# Lights.net
KiCad netlist of a schematic drawn in Altium Designer
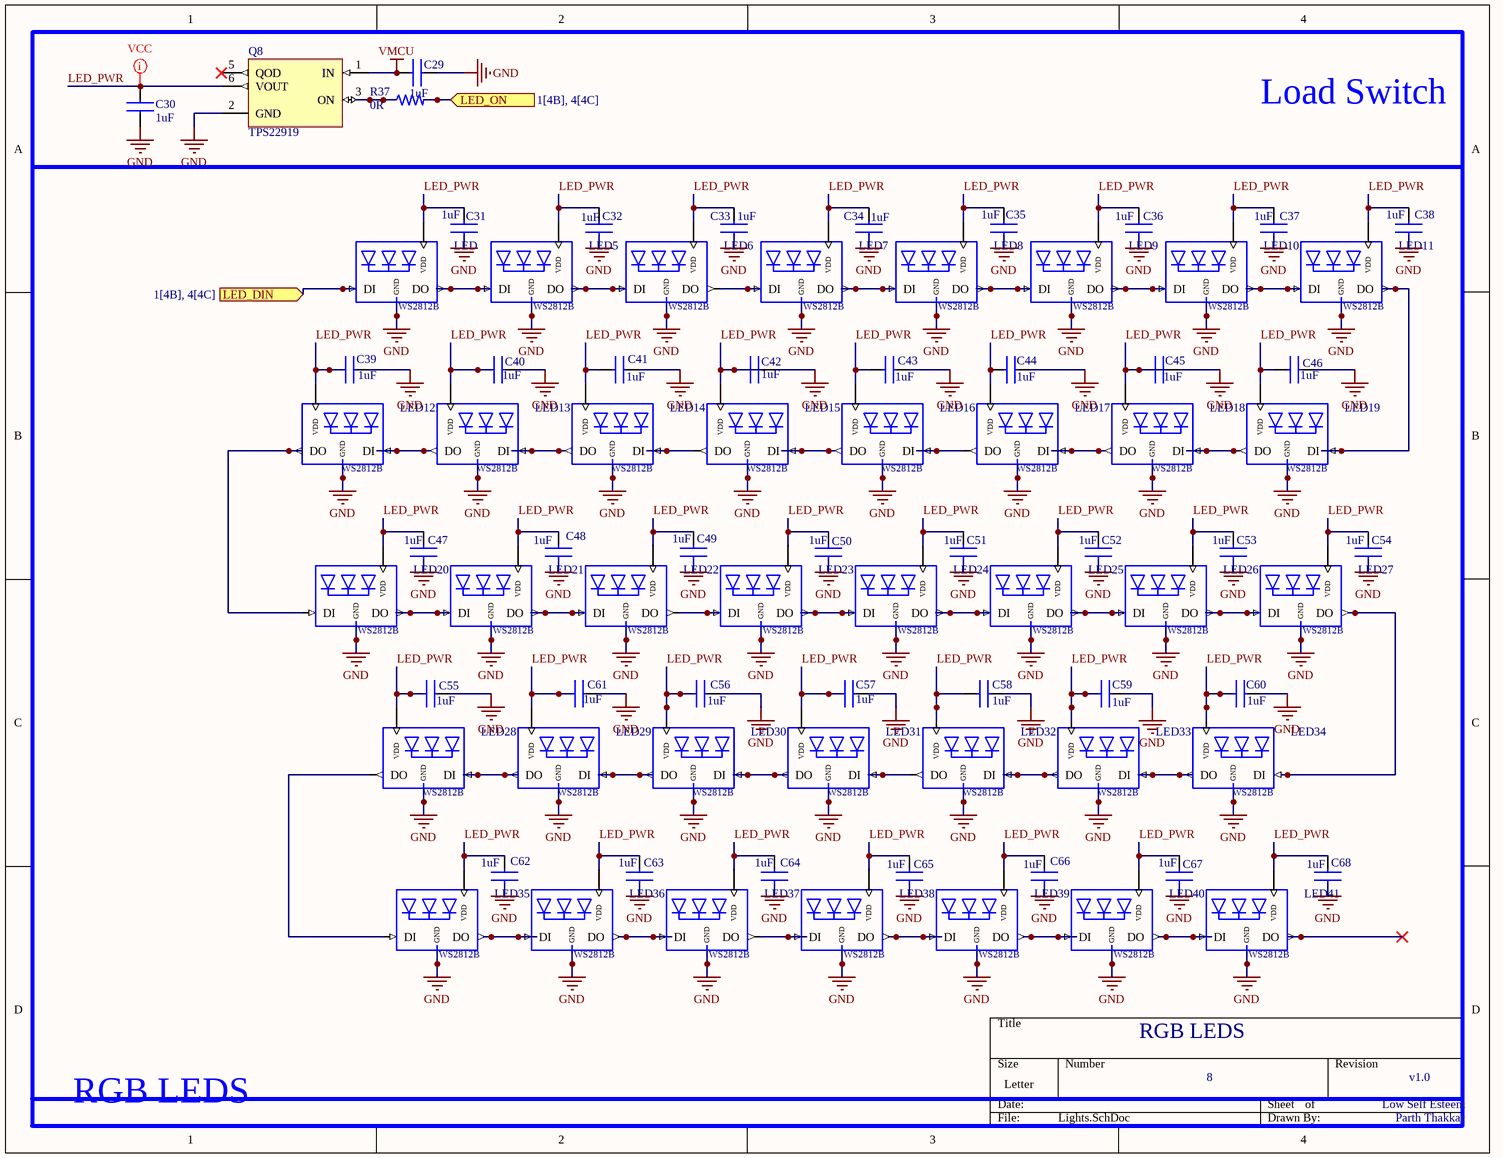
[diagram p0: Lights.SchDoc]

(export (version "E")
  (design (tool "Eeschema 10.0.6"))
  (components
    (comp (ref "C29")
      (value "1uF")
      (footprint "Capacitor 0603")
      (fields
        (field (name "MANUFACTURER") "Murata")
        (field (name "MANUFACTURER PART NUMBER") "GRM188R61A105KA61D")
        (field (name "Comment") "CAP 1uF 10V 0603")
      )
      (libsource (lib "Keyboard_parts") (part "CAP 1uF 10V 0603"))
    )
    (comp (ref "C30")
      (value "1uF")
      (footprint "CAPACITOR 0805")
      (description "Multilayer Ceramic Capacitor, 1 uF, 10 V, ± 20%, X5R, 0201 [0603 Metric]")
      (fields
        (field (name "MANUFACTURER") "Murata")
        (field (name "MANUFACTURER PART NUMBER") "GRM033R61A105ME15D")
      )
      (libsource (lib "Keyboard_parts") (part "CAP 47uF 10V 0805"))
    )
    (comp (ref "C31")
      (value "1uF")
      (footprint "Capacitor 0603")
      (fields
        (field (name "MANUFACTURER") "Murata")
        (field (name "MANUFACTURER PART NUMBER") "GRM188R61A105KA61D")
        (field (name "Comment") "CAP 1uF 10V 0603")
      )
      (libsource (lib "Keyboard_parts") (part "CAP 1uF 10V 0603"))
    )
    (comp (ref "C32")
      (value "1uF")
      (footprint "Capacitor 0603")
      (fields
        (field (name "MANUFACTURER") "Murata")
        (field (name "MANUFACTURER PART NUMBER") "GRM188R61A105KA61D")
        (field (name "Comment") "CAP 1uF 10V 0603")
      )
      (libsource (lib "Keyboard_parts") (part "CAP 1uF 10V 0603"))
    )
    (comp (ref "C33")
      (value "1uF")
      (footprint "Capacitor 0603")
      (fields
        (field (name "MANUFACTURER") "Murata")
        (field (name "MANUFACTURER PART NUMBER") "GRM188R61A105KA61D")
        (field (name "Comment") "CAP 1uF 10V 0603")
      )
      (libsource (lib "Keyboard_parts") (part "CAP 1uF 10V 0603"))
    )
    (comp (ref "C34")
      (value "1uF")
      (footprint "Capacitor 0603")
      (fields
        (field (name "MANUFACTURER") "Murata")
        (field (name "MANUFACTURER PART NUMBER") "GRM188R61A105KA61D")
        (field (name "Comment") "CAP 1uF 10V 0603")
      )
      (libsource (lib "Keyboard_parts") (part "CAP 1uF 10V 0603"))
    )
    (comp (ref "C35")
      (value "1uF")
      (footprint "Capacitor 0603")
      (fields
        (field (name "MANUFACTURER") "Murata")
        (field (name "MANUFACTURER PART NUMBER") "GRM188R61A105KA61D")
        (field (name "Comment") "CAP 1uF 10V 0603")
      )
      (libsource (lib "Keyboard_parts") (part "CAP 1uF 10V 0603"))
    )
    (comp (ref "C36")
      (value "1uF")
      (footprint "Capacitor 0603")
      (fields
        (field (name "MANUFACTURER") "Murata")
        (field (name "MANUFACTURER PART NUMBER") "GRM188R61A105KA61D")
        (field (name "Comment") "CAP 1uF 10V 0603")
      )
      (libsource (lib "Keyboard_parts") (part "CAP 1uF 10V 0603"))
    )
    (comp (ref "C37")
      (value "1uF")
      (footprint "Capacitor 0603")
      (fields
        (field (name "MANUFACTURER") "Murata")
        (field (name "MANUFACTURER PART NUMBER") "GRM188R61A105KA61D")
        (field (name "Comment") "CAP 1uF 10V 0603")
      )
      (libsource (lib "Keyboard_parts") (part "CAP 1uF 10V 0603"))
    )
    (comp (ref "C38")
      (value "1uF")
      (footprint "Capacitor 0603")
      (fields
        (field (name "MANUFACTURER") "Murata")
        (field (name "MANUFACTURER PART NUMBER") "GRM188R61A105KA61D")
        (field (name "Comment") "CAP 1uF 10V 0603")
      )
      (libsource (lib "Keyboard_parts") (part "CAP 1uF 10V 0603"))
    )
    (comp (ref "C39")
      (value "1uF")
      (footprint "Capacitor 0603")
      (fields
        (field (name "MANUFACTURER") "Murata")
        (field (name "MANUFACTURER PART NUMBER") "GRM188R61A105KA61D")
        (field (name "Comment") "CAP 1uF 10V 0603")
      )
      (libsource (lib "Keyboard_parts") (part "CAP 1uF 10V 0603"))
    )
    (comp (ref "C40")
      (value "1uF")
      (footprint "Capacitor 0603")
      (fields
        (field (name "MANUFACTURER") "Murata")
        (field (name "MANUFACTURER PART NUMBER") "GRM188R61A105KA61D")
        (field (name "Comment") "CAP 1uF 10V 0603")
      )
      (libsource (lib "Keyboard_parts") (part "CAP 1uF 10V 0603"))
    )
    (comp (ref "C41")
      (value "1uF")
      (footprint "Capacitor 0603")
      (fields
        (field (name "MANUFACTURER") "Murata")
        (field (name "MANUFACTURER PART NUMBER") "GRM188R61A105KA61D")
        (field (name "Comment") "CAP 1uF 10V 0603")
      )
      (libsource (lib "Keyboard_parts") (part "CAP 1uF 10V 0603"))
    )
    (comp (ref "C42")
      (value "1uF")
      (footprint "Capacitor 0603")
      (fields
        (field (name "MANUFACTURER") "Murata")
        (field (name "MANUFACTURER PART NUMBER") "GRM188R61A105KA61D")
        (field (name "Comment") "CAP 1uF 10V 0603")
      )
      (libsource (lib "Keyboard_parts") (part "CAP 1uF 10V 0603"))
    )
    (comp (ref "C43")
      (value "1uF")
      (footprint "Capacitor 0603")
      (fields
        (field (name "MANUFACTURER") "Murata")
        (field (name "MANUFACTURER PART NUMBER") "GRM188R61A105KA61D")
        (field (name "Comment") "CAP 1uF 10V 0603")
      )
      (libsource (lib "Keyboard_parts") (part "CAP 1uF 10V 0603"))
    )
    (comp (ref "C44")
      (value "1uF")
      (footprint "Capacitor 0603")
      (fields
        (field (name "MANUFACTURER") "Murata")
        (field (name "MANUFACTURER PART NUMBER") "GRM188R61A105KA61D")
        (field (name "Comment") "CAP 1uF 10V 0603")
      )
      (libsource (lib "Keyboard_parts") (part "CAP 1uF 10V 0603"))
    )
    (comp (ref "C45")
      (value "1uF")
      (footprint "Capacitor 0603")
      (fields
        (field (name "MANUFACTURER") "Murata")
        (field (name "MANUFACTURER PART NUMBER") "GRM188R61A105KA61D")
        (field (name "Comment") "CAP 1uF 10V 0603")
      )
      (libsource (lib "Keyboard_parts") (part "CAP 1uF 10V 0603"))
    )
    (comp (ref "C46")
      (value "1uF")
      (footprint "Capacitor 0603")
      (fields
        (field (name "MANUFACTURER") "Murata")
        (field (name "MANUFACTURER PART NUMBER") "GRM188R61A105KA61D")
        (field (name "Comment") "CAP 1uF 10V 0603")
      )
      (libsource (lib "Keyboard_parts") (part "CAP 1uF 10V 0603"))
    )
    (comp (ref "C47")
      (value "1uF")
      (footprint "Capacitor 0603")
      (fields
        (field (name "MANUFACTURER") "Murata")
        (field (name "MANUFACTURER PART NUMBER") "GRM188R61A105KA61D")
        (field (name "Comment") "CAP 1uF 10V 0603")
      )
      (libsource (lib "Keyboard_parts") (part "CAP 1uF 10V 0603"))
    )
    (comp (ref "C48")
      (value "1uF")
      (footprint "Capacitor 0603")
      (fields
        (field (name "MANUFACTURER") "Murata")
        (field (name "MANUFACTURER PART NUMBER") "GRM188R61A105KA61D")
        (field (name "Comment") "CAP 1uF 10V 0603")
      )
      (libsource (lib "Keyboard_parts") (part "CAP 1uF 10V 0603"))
    )
    (comp (ref "C49")
      (value "1uF")
      (footprint "Capacitor 0603")
      (fields
        (field (name "MANUFACTURER") "Murata")
        (field (name "MANUFACTURER PART NUMBER") "GRM188R61A105KA61D")
        (field (name "Comment") "CAP 1uF 10V 0603")
      )
      (libsource (lib "Keyboard_parts") (part "CAP 1uF 10V 0603"))
    )
    (comp (ref "C50")
      (value "1uF")
      (footprint "Capacitor 0603")
      (fields
        (field (name "MANUFACTURER") "Murata")
        (field (name "MANUFACTURER PART NUMBER") "GRM188R61A105KA61D")
        (field (name "Comment") "CAP 1uF 10V 0603")
      )
      (libsource (lib "Keyboard_parts") (part "CAP 1uF 10V 0603"))
    )
    (comp (ref "C51")
      (value "1uF")
      (footprint "Capacitor 0603")
      (fields
        (field (name "MANUFACTURER") "Murata")
        (field (name "MANUFACTURER PART NUMBER") "GRM188R61A105KA61D")
        (field (name "Comment") "CAP 1uF 10V 0603")
      )
      (libsource (lib "Keyboard_parts") (part "CAP 1uF 10V 0603"))
    )
    (comp (ref "C52")
      (value "1uF")
      (footprint "Capacitor 0603")
      (fields
        (field (name "MANUFACTURER") "Murata")
        (field (name "MANUFACTURER PART NUMBER") "GRM188R61A105KA61D")
        (field (name "Comment") "CAP 1uF 10V 0603")
      )
      (libsource (lib "Keyboard_parts") (part "CAP 1uF 10V 0603"))
    )
    (comp (ref "C53")
      (value "1uF")
      (footprint "Capacitor 0603")
      (fields
        (field (name "MANUFACTURER") "Murata")
        (field (name "MANUFACTURER PART NUMBER") "GRM188R61A105KA61D")
        (field (name "Comment") "CAP 1uF 10V 0603")
      )
      (libsource (lib "Keyboard_parts") (part "CAP 1uF 10V 0603"))
    )
    (comp (ref "C54")
      (value "1uF")
      (footprint "Capacitor 0603")
      (fields
        (field (name "MANUFACTURER") "Murata")
        (field (name "MANUFACTURER PART NUMBER") "GRM188R61A105KA61D")
        (field (name "Comment") "CAP 1uF 10V 0603")
      )
      (libsource (lib "Keyboard_parts") (part "CAP 1uF 10V 0603"))
    )
    (comp (ref "C55")
      (value "1uF")
      (footprint "Capacitor 0603")
      (fields
        (field (name "MANUFACTURER") "Murata")
        (field (name "MANUFACTURER PART NUMBER") "GRM188R61A105KA61D")
        (field (name "Comment") "CAP 1uF 10V 0603")
      )
      (libsource (lib "Keyboard_parts") (part "CAP 1uF 10V 0603"))
    )
    (comp (ref "C56")
      (value "1uF")
      (footprint "Capacitor 0603")
      (fields
        (field (name "MANUFACTURER") "Murata")
        (field (name "MANUFACTURER PART NUMBER") "GRM188R61A105KA61D")
        (field (name "Comment") "CAP 1uF 10V 0603")
      )
      (libsource (lib "Keyboard_parts") (part "CAP 1uF 10V 0603"))
    )
    (comp (ref "C57")
      (value "1uF")
      (footprint "Capacitor 0603")
      (fields
        (field (name "MANUFACTURER") "Murata")
        (field (name "MANUFACTURER PART NUMBER") "GRM188R61A105KA61D")
        (field (name "Comment") "CAP 1uF 10V 0603")
      )
      (libsource (lib "Keyboard_parts") (part "CAP 1uF 10V 0603"))
    )
    (comp (ref "C58")
      (value "1uF")
      (footprint "Capacitor 0603")
      (fields
        (field (name "MANUFACTURER") "Murata")
        (field (name "MANUFACTURER PART NUMBER") "GRM188R61A105KA61D")
        (field (name "Comment") "CAP 1uF 10V 0603")
      )
      (libsource (lib "Keyboard_parts") (part "CAP 1uF 10V 0603"))
    )
    (comp (ref "C59")
      (value "1uF")
      (footprint "Capacitor 0603")
      (fields
        (field (name "MANUFACTURER") "Murata")
        (field (name "MANUFACTURER PART NUMBER") "GRM188R61A105KA61D")
        (field (name "Comment") "CAP 1uF 10V 0603")
      )
      (libsource (lib "Keyboard_parts") (part "CAP 1uF 10V 0603"))
    )
    (comp (ref "C60")
      (value "1uF")
      (footprint "Capacitor 0603")
      (fields
        (field (name "MANUFACTURER") "Murata")
        (field (name "MANUFACTURER PART NUMBER") "GRM188R61A105KA61D")
        (field (name "Comment") "CAP 1uF 10V 0603")
      )
      (libsource (lib "Keyboard_parts") (part "CAP 1uF 10V 0603"))
    )
    (comp (ref "C61")
      (value "1uF")
      (footprint "Capacitor 0603")
      (fields
        (field (name "MANUFACTURER") "Murata")
        (field (name "MANUFACTURER PART NUMBER") "GRM188R61A105KA61D")
        (field (name "Comment") "CAP 1uF 10V 0603")
      )
      (libsource (lib "Keyboard_parts") (part "CAP 1uF 10V 0603"))
    )
    (comp (ref "C62")
      (value "1uF")
      (footprint "Capacitor 0603")
      (fields
        (field (name "MANUFACTURER") "Murata")
        (field (name "MANUFACTURER PART NUMBER") "GRM188R61A105KA61D")
        (field (name "Comment") "CAP 1uF 10V 0603")
      )
      (libsource (lib "Keyboard_parts") (part "CAP 1uF 10V 0603"))
    )
    (comp (ref "C63")
      (value "1uF")
      (footprint "Capacitor 0603")
      (fields
        (field (name "MANUFACTURER") "Murata")
        (field (name "MANUFACTURER PART NUMBER") "GRM188R61A105KA61D")
        (field (name "Comment") "CAP 1uF 10V 0603")
      )
      (libsource (lib "Keyboard_parts") (part "CAP 1uF 10V 0603"))
    )
    (comp (ref "C64")
      (value "1uF")
      (footprint "Capacitor 0603")
      (fields
        (field (name "MANUFACTURER") "Murata")
        (field (name "MANUFACTURER PART NUMBER") "GRM188R61A105KA61D")
        (field (name "Comment") "CAP 1uF 10V 0603")
      )
      (libsource (lib "Keyboard_parts") (part "CAP 1uF 10V 0603"))
    )
    (comp (ref "C65")
      (value "1uF")
      (footprint "Capacitor 0603")
      (fields
        (field (name "MANUFACTURER") "Murata")
        (field (name "MANUFACTURER PART NUMBER") "GRM188R61A105KA61D")
        (field (name "Comment") "CAP 1uF 10V 0603")
      )
      (libsource (lib "Keyboard_parts") (part "CAP 1uF 10V 0603"))
    )
    (comp (ref "C66")
      (value "1uF")
      (footprint "Capacitor 0603")
      (fields
        (field (name "MANUFACTURER") "Murata")
        (field (name "MANUFACTURER PART NUMBER") "GRM188R61A105KA61D")
        (field (name "Comment") "CAP 1uF 10V 0603")
      )
      (libsource (lib "Keyboard_parts") (part "CAP 1uF 10V 0603"))
    )
    (comp (ref "C67")
      (value "1uF")
      (footprint "Capacitor 0603")
      (fields
        (field (name "MANUFACTURER") "Murata")
        (field (name "MANUFACTURER PART NUMBER") "GRM188R61A105KA61D")
        (field (name "Comment") "CAP 1uF 10V 0603")
      )
      (libsource (lib "Keyboard_parts") (part "CAP 1uF 10V 0603"))
    )
    (comp (ref "C68")
      (value "1uF")
      (footprint "Capacitor 0603")
      (fields
        (field (name "MANUFACTURER") "Murata")
        (field (name "MANUFACTURER PART NUMBER") "GRM188R61A105KA61D")
        (field (name "Comment") "CAP 1uF 10V 0603")
      )
      (libsource (lib "Keyboard_parts") (part "CAP 1uF 10V 0603"))
    )
    (comp (ref "LED")
      (value "WS2812B")
      (footprint "WS2812B")
      (description "NeoPixel Nano 2020 RGB LEDs - 10-Pack ¦ Adafruit Industries 4684")
      (fields
        (field (name "MANUFACTURER") "Inolux")
        (field (name "MANUFACTURER PART NUMBER") "B3DK3BRG-05C000113U1930")
      )
      (libsource (lib "Keyboard_parts") (part "WS2812B"))
    )
    (comp (ref "LED5")
      (value "WS2812B")
      (footprint "WS2812B")
      (description "NeoPixel Nano 2020 RGB LEDs - 10-Pack ¦ Adafruit Industries 4684")
      (fields
        (field (name "MANUFACTURER") "Inolux")
        (field (name "MANUFACTURER PART NUMBER") "B3DK3BRG-05C000113U1930")
      )
      (libsource (lib "Keyboard_parts") (part "WS2812B"))
    )
    (comp (ref "LED6")
      (value "WS2812B")
      (footprint "WS2812B")
      (description "NeoPixel Nano 2020 RGB LEDs - 10-Pack ¦ Adafruit Industries 4684")
      (fields
        (field (name "MANUFACTURER") "Inolux")
        (field (name "MANUFACTURER PART NUMBER") "B3DK3BRG-05C000113U1930")
      )
      (libsource (lib "Keyboard_parts") (part "WS2812B"))
    )
    (comp (ref "LED7")
      (value "WS2812B")
      (footprint "WS2812B")
      (description "NeoPixel Nano 2020 RGB LEDs - 10-Pack ¦ Adafruit Industries 4684")
      (fields
        (field (name "MANUFACTURER") "Inolux")
        (field (name "MANUFACTURER PART NUMBER") "B3DK3BRG-05C000113U1930")
      )
      (libsource (lib "Keyboard_parts") (part "WS2812B"))
    )
    (comp (ref "LED8")
      (value "WS2812B")
      (footprint "WS2812B")
      (description "NeoPixel Nano 2020 RGB LEDs - 10-Pack ¦ Adafruit Industries 4684")
      (fields
        (field (name "MANUFACTURER") "Inolux")
        (field (name "MANUFACTURER PART NUMBER") "B3DK3BRG-05C000113U1930")
      )
      (libsource (lib "Keyboard_parts") (part "WS2812B"))
    )
    (comp (ref "LED9")
      (value "WS2812B")
      (footprint "WS2812B")
      (description "NeoPixel Nano 2020 RGB LEDs - 10-Pack ¦ Adafruit Industries 4684")
      (fields
        (field (name "MANUFACTURER") "Inolux")
        (field (name "MANUFACTURER PART NUMBER") "B3DK3BRG-05C000113U1930")
      )
      (libsource (lib "Keyboard_parts") (part "WS2812B"))
    )
    (comp (ref "LED10")
      (value "WS2812B")
      (footprint "WS2812B")
      (description "NeoPixel Nano 2020 RGB LEDs - 10-Pack ¦ Adafruit Industries 4684")
      (fields
        (field (name "MANUFACTURER") "Inolux")
        (field (name "MANUFACTURER PART NUMBER") "B3DK3BRG-05C000113U1930")
      )
      (libsource (lib "Keyboard_parts") (part "WS2812B"))
    )
    (comp (ref "LED11")
      (value "WS2812B")
      (footprint "WS2812B")
      (description "NeoPixel Nano 2020 RGB LEDs - 10-Pack ¦ Adafruit Industries 4684")
      (fields
        (field (name "MANUFACTURER") "Inolux")
        (field (name "MANUFACTURER PART NUMBER") "B3DK3BRG-05C000113U1930")
      )
      (libsource (lib "Keyboard_parts") (part "WS2812B"))
    )
    (comp (ref "LED12")
      (value "WS2812B")
      (footprint "WS2812B")
      (description "NeoPixel Nano 2020 RGB LEDs - 10-Pack ¦ Adafruit Industries 4684")
      (fields
        (field (name "MANUFACTURER") "Inolux")
        (field (name "MANUFACTURER PART NUMBER") "B3DK3BRG-05C000113U1930")
      )
      (libsource (lib "Keyboard_parts") (part "WS2812B"))
    )
    (comp (ref "LED13")
      (value "WS2812B")
      (footprint "WS2812B")
      (description "NeoPixel Nano 2020 RGB LEDs - 10-Pack ¦ Adafruit Industries 4684")
      (fields
        (field (name "MANUFACTURER") "Inolux")
        (field (name "MANUFACTURER PART NUMBER") "B3DK3BRG-05C000113U1930")
      )
      (libsource (lib "Keyboard_parts") (part "WS2812B"))
    )
    (comp (ref "LED14")
      (value "WS2812B")
      (footprint "WS2812B")
      (description "NeoPixel Nano 2020 RGB LEDs - 10-Pack ¦ Adafruit Industries 4684")
      (fields
        (field (name "MANUFACTURER") "Inolux")
        (field (name "MANUFACTURER PART NUMBER") "B3DK3BRG-05C000113U1930")
      )
      (libsource (lib "Keyboard_parts") (part "WS2812B"))
    )
    (comp (ref "LED15")
      (value "WS2812B")
      (footprint "WS2812B")
      (description "NeoPixel Nano 2020 RGB LEDs - 10-Pack ¦ Adafruit Industries 4684")
      (fields
        (field (name "MANUFACTURER") "Inolux")
        (field (name "MANUFACTURER PART NUMBER") "B3DK3BRG-05C000113U1930")
      )
      (libsource (lib "Keyboard_parts") (part "WS2812B"))
    )
    (comp (ref "LED16")
      (value "WS2812B")
      (footprint "WS2812B")
      (description "NeoPixel Nano 2020 RGB LEDs - 10-Pack ¦ Adafruit Industries 4684")
      (fields
        (field (name "MANUFACTURER") "Inolux")
        (field (name "MANUFACTURER PART NUMBER") "B3DK3BRG-05C000113U1930")
      )
      (libsource (lib "Keyboard_parts") (part "WS2812B"))
    )
    (comp (ref "LED17")
      (value "WS2812B")
      (footprint "WS2812B")
      (description "NeoPixel Nano 2020 RGB LEDs - 10-Pack ¦ Adafruit Industries 4684")
      (fields
        (field (name "MANUFACTURER") "Inolux")
        (field (name "MANUFACTURER PART NUMBER") "B3DK3BRG-05C000113U1930")
      )
      (libsource (lib "Keyboard_parts") (part "WS2812B"))
    )
    (comp (ref "LED18")
      (value "WS2812B")
      (footprint "WS2812B")
      (description "NeoPixel Nano 2020 RGB LEDs - 10-Pack ¦ Adafruit Industries 4684")
      (fields
        (field (name "MANUFACTURER") "Inolux")
        (field (name "MANUFACTURER PART NUMBER") "B3DK3BRG-05C000113U1930")
      )
      (libsource (lib "Keyboard_parts") (part "WS2812B"))
    )
    (comp (ref "LED19")
      (value "WS2812B")
      (footprint "WS2812B")
      (description "NeoPixel Nano 2020 RGB LEDs - 10-Pack ¦ Adafruit Industries 4684")
      (fields
        (field (name "MANUFACTURER") "Inolux")
        (field (name "MANUFACTURER PART NUMBER") "B3DK3BRG-05C000113U1930")
      )
      (libsource (lib "Keyboard_parts") (part "WS2812B"))
    )
    (comp (ref "LED20")
      (value "WS2812B")
      (footprint "WS2812B")
      (description "NeoPixel Nano 2020 RGB LEDs - 10-Pack ¦ Adafruit Industries 4684")
      (fields
        (field (name "MANUFACTURER") "Inolux")
        (field (name "MANUFACTURER PART NUMBER") "B3DK3BRG-05C000113U1930")
      )
      (libsource (lib "Keyboard_parts") (part "WS2812B"))
    )
    (comp (ref "LED21")
      (value "WS2812B")
      (footprint "WS2812B")
      (description "NeoPixel Nano 2020 RGB LEDs - 10-Pack ¦ Adafruit Industries 4684")
      (fields
        (field (name "MANUFACTURER") "Inolux")
        (field (name "MANUFACTURER PART NUMBER") "B3DK3BRG-05C000113U1930")
      )
      (libsource (lib "Keyboard_parts") (part "WS2812B"))
    )
    (comp (ref "LED22")
      (value "WS2812B")
      (footprint "WS2812B")
      (description "NeoPixel Nano 2020 RGB LEDs - 10-Pack ¦ Adafruit Industries 4684")
      (fields
        (field (name "MANUFACTURER") "Inolux")
        (field (name "MANUFACTURER PART NUMBER") "B3DK3BRG-05C000113U1930")
      )
      (libsource (lib "Keyboard_parts") (part "WS2812B"))
    )
    (comp (ref "LED23")
      (value "WS2812B")
      (footprint "WS2812B")
      (description "NeoPixel Nano 2020 RGB LEDs - 10-Pack ¦ Adafruit Industries 4684")
      (fields
        (field (name "MANUFACTURER") "Inolux")
        (field (name "MANUFACTURER PART NUMBER") "B3DK3BRG-05C000113U1930")
      )
      (libsource (lib "Keyboard_parts") (part "WS2812B"))
    )
    (comp (ref "LED24")
      (value "WS2812B")
      (footprint "WS2812B")
      (description "NeoPixel Nano 2020 RGB LEDs - 10-Pack ¦ Adafruit Industries 4684")
      (fields
        (field (name "MANUFACTURER") "Inolux")
        (field (name "MANUFACTURER PART NUMBER") "B3DK3BRG-05C000113U1930")
      )
      (libsource (lib "Keyboard_parts") (part "WS2812B"))
    )
    (comp (ref "LED25")
      (value "WS2812B")
      (footprint "WS2812B")
      (description "NeoPixel Nano 2020 RGB LEDs - 10-Pack ¦ Adafruit Industries 4684")
      (fields
        (field (name "MANUFACTURER") "Inolux")
        (field (name "MANUFACTURER PART NUMBER") "B3DK3BRG-05C000113U1930")
      )
      (libsource (lib "Keyboard_parts") (part "WS2812B"))
    )
    (comp (ref "LED26")
      (value "WS2812B")
      (footprint "WS2812B")
      (description "NeoPixel Nano 2020 RGB LEDs - 10-Pack ¦ Adafruit Industries 4684")
      (fields
        (field (name "MANUFACTURER") "Inolux")
        (field (name "MANUFACTURER PART NUMBER") "B3DK3BRG-05C000113U1930")
      )
      (libsource (lib "Keyboard_parts") (part "WS2812B"))
    )
    (comp (ref "LED27")
      (value "WS2812B")
      (footprint "WS2812B")
      (description "NeoPixel Nano 2020 RGB LEDs - 10-Pack ¦ Adafruit Industries 4684")
      (fields
        (field (name "MANUFACTURER") "Inolux")
        (field (name "MANUFACTURER PART NUMBER") "B3DK3BRG-05C000113U1930")
      )
      (libsource (lib "Keyboard_parts") (part "WS2812B"))
    )
    (comp (ref "LED28")
      (value "WS2812B")
      (footprint "WS2812B")
      (description "NeoPixel Nano 2020 RGB LEDs - 10-Pack ¦ Adafruit Industries 4684")
      (fields
        (field (name "MANUFACTURER") "Inolux")
        (field (name "MANUFACTURER PART NUMBER") "B3DK3BRG-05C000113U1930")
      )
      (libsource (lib "Keyboard_parts") (part "WS2812B"))
    )
    (comp (ref "LED29")
      (value "WS2812B")
      (footprint "WS2812B")
      (description "NeoPixel Nano 2020 RGB LEDs - 10-Pack ¦ Adafruit Industries 4684")
      (fields
        (field (name "MANUFACTURER") "Inolux")
        (field (name "MANUFACTURER PART NUMBER") "B3DK3BRG-05C000113U1930")
      )
      (libsource (lib "Keyboard_parts") (part "WS2812B"))
    )
    (comp (ref "LED30")
      (value "WS2812B")
      (footprint "WS2812B")
      (description "NeoPixel Nano 2020 RGB LEDs - 10-Pack ¦ Adafruit Industries 4684")
      (fields
        (field (name "MANUFACTURER") "Inolux")
        (field (name "MANUFACTURER PART NUMBER") "B3DK3BRG-05C000113U1930")
      )
      (libsource (lib "Keyboard_parts") (part "WS2812B"))
    )
    (comp (ref "LED31")
      (value "WS2812B")
      (footprint "WS2812B")
      (description "NeoPixel Nano 2020 RGB LEDs - 10-Pack ¦ Adafruit Industries 4684")
      (fields
        (field (name "MANUFACTURER") "Inolux")
        (field (name "MANUFACTURER PART NUMBER") "B3DK3BRG-05C000113U1930")
      )
      (libsource (lib "Keyboard_parts") (part "WS2812B"))
    )
    (comp (ref "LED32")
      (value "WS2812B")
      (footprint "WS2812B")
      (description "NeoPixel Nano 2020 RGB LEDs - 10-Pack ¦ Adafruit Industries 4684")
      (fields
        (field (name "MANUFACTURER") "Inolux")
        (field (name "MANUFACTURER PART NUMBER") "B3DK3BRG-05C000113U1930")
      )
      (libsource (lib "Keyboard_parts") (part "WS2812B"))
    )
    (comp (ref "LED33")
      (value "WS2812B")
      (footprint "WS2812B")
      (description "NeoPixel Nano 2020 RGB LEDs - 10-Pack ¦ Adafruit Industries 4684")
      (fields
        (field (name "MANUFACTURER") "Inolux")
        (field (name "MANUFACTURER PART NUMBER") "B3DK3BRG-05C000113U1930")
      )
      (libsource (lib "Keyboard_parts") (part "WS2812B"))
    )
    (comp (ref "LED34")
      (value "WS2812B")
      (footprint "WS2812B")
      (description "NeoPixel Nano 2020 RGB LEDs - 10-Pack ¦ Adafruit Industries 4684")
      (fields
        (field (name "MANUFACTURER") "Inolux")
        (field (name "MANUFACTURER PART NUMBER") "B3DK3BRG-05C000113U1930")
      )
      (libsource (lib "Keyboard_parts") (part "WS2812B"))
    )
    (comp (ref "LED35")
      (value "WS2812B")
      (footprint "WS2812B")
      (description "NeoPixel Nano 2020 RGB LEDs - 10-Pack ¦ Adafruit Industries 4684")
      (fields
        (field (name "MANUFACTURER") "Inolux")
        (field (name "MANUFACTURER PART NUMBER") "B3DK3BRG-05C000113U1930")
      )
      (libsource (lib "Keyboard_parts") (part "WS2812B"))
    )
    (comp (ref "LED36")
      (value "WS2812B")
      (footprint "WS2812B")
      (description "NeoPixel Nano 2020 RGB LEDs - 10-Pack ¦ Adafruit Industries 4684")
      (fields
        (field (name "MANUFACTURER") "Inolux")
        (field (name "MANUFACTURER PART NUMBER") "B3DK3BRG-05C000113U1930")
      )
      (libsource (lib "Keyboard_parts") (part "WS2812B"))
    )
    (comp (ref "LED37")
      (value "WS2812B")
      (footprint "WS2812B")
      (description "NeoPixel Nano 2020 RGB LEDs - 10-Pack ¦ Adafruit Industries 4684")
      (fields
        (field (name "MANUFACTURER") "Inolux")
        (field (name "MANUFACTURER PART NUMBER") "B3DK3BRG-05C000113U1930")
      )
      (libsource (lib "Keyboard_parts") (part "WS2812B"))
    )
    (comp (ref "LED38")
      (value "WS2812B")
      (footprint "WS2812B")
      (description "NeoPixel Nano 2020 RGB LEDs - 10-Pack ¦ Adafruit Industries 4684")
      (fields
        (field (name "MANUFACTURER") "Inolux")
        (field (name "MANUFACTURER PART NUMBER") "B3DK3BRG-05C000113U1930")
      )
      (libsource (lib "Keyboard_parts") (part "WS2812B"))
    )
    (comp (ref "LED39")
      (value "WS2812B")
      (footprint "WS2812B")
      (description "NeoPixel Nano 2020 RGB LEDs - 10-Pack ¦ Adafruit Industries 4684")
      (fields
        (field (name "MANUFACTURER") "Inolux")
        (field (name "MANUFACTURER PART NUMBER") "B3DK3BRG-05C000113U1930")
      )
      (libsource (lib "Keyboard_parts") (part "WS2812B"))
    )
    (comp (ref "LED40")
      (value "WS2812B")
      (footprint "WS2812B")
      (description "NeoPixel Nano 2020 RGB LEDs - 10-Pack ¦ Adafruit Industries 4684")
      (fields
        (field (name "MANUFACTURER") "Inolux")
        (field (name "MANUFACTURER PART NUMBER") "B3DK3BRG-05C000113U1930")
      )
      (libsource (lib "Keyboard_parts") (part "WS2812B"))
    )
    (comp (ref "LED41")
      (value "WS2812B")
      (footprint "WS2812B")
      (description "NeoPixel Nano 2020 RGB LEDs - 10-Pack ¦ Adafruit Industries 4684")
      (fields
        (field (name "MANUFACTURER") "Inolux")
        (field (name "MANUFACTURER PART NUMBER") "B3DK3BRG-05C000113U1930")
      )
      (libsource (lib "Keyboard_parts") (part "WS2812B"))
    )
    (comp (ref "Q8")
      (value "TPS22919")
      (footprint "TPS22919DCKR - Load SW")
      (description "Buffer/Inverter Based Peripheral Driver, 3A, PDSO6")
      (fields
        (field (name "MANUFACTURER") "Texas Instruments")
        (field (name "MANUFACTURER PART NUMBER") "TPS22919DCKR")
      )
      (libsource (lib "Keyboard_parts") (part "TPS22919"))
    )
    (comp (ref "R37")
      (value "0R")
      (footprint "Resistor 0402")
      (description "Metal Glaze/thick Film, 0.0625W, 0ohm, Surface Mount, 0402")
      (fields
        (field (name "MANUFACTURER") "Yageo")
        (field (name "MANUFACTURER PART NUMBER") "RC0402JR-070RL")
      )
      (libsource (lib "Keyboard_parts") (part "RES 0R 0402"))
    )
  )
  (nets
    (net (code "2") (name "/LED_DIN") (class "Default")
      (node (ref "LED") (pin "3-DI") (pinfunction "DI_3-DI") (pintype "input"))
    )
    (net (code "3") (name "/LED_ON") (class "Default")
      (node (ref "R37") (pin "2") (pinfunction "2_2") (pintype "passive"))
    )
    (net (code "4") (name "/LED_PWR") (class "Default")
      (node (ref "C30") (pin "1") (pinfunction "1_1") (pintype "passive"))
      (node (ref "C31") (pin "1") (pinfunction "1_1") (pintype "passive"))
      (node (ref "C32") (pin "1") (pinfunction "1_1") (pintype "passive"))
      (node (ref "C33") (pin "1") (pinfunction "1_1") (pintype "passive"))
      (node (ref "C34") (pin "1") (pinfunction "1_1") (pintype "passive"))
      (node (ref "C35") (pin "1") (pinfunction "1_1") (pintype "passive"))
      (node (ref "C36") (pin "1") (pinfunction "1_1") (pintype "passive"))
      (node (ref "C37") (pin "1") (pinfunction "1_1") (pintype "passive"))
      (node (ref "C38") (pin "1") (pinfunction "1_1") (pintype "passive"))
      (node (ref "C39") (pin "1") (pinfunction "1_1") (pintype "passive"))
      (node (ref "C40") (pin "1") (pinfunction "1_1") (pintype "passive"))
      (node (ref "C41") (pin "1") (pinfunction "1_1") (pintype "passive"))
      (node (ref "C42") (pin "1") (pinfunction "1_1") (pintype "passive"))
      (node (ref "C43") (pin "1") (pinfunction "1_1") (pintype "passive"))
      (node (ref "C44") (pin "1") (pinfunction "1_1") (pintype "passive"))
      (node (ref "C45") (pin "1") (pinfunction "1_1") (pintype "passive"))
      (node (ref "C46") (pin "1") (pinfunction "1_1") (pintype "passive"))
      (node (ref "C47") (pin "1") (pinfunction "1_1") (pintype "passive"))
      (node (ref "C48") (pin "1") (pinfunction "1_1") (pintype "passive"))
      (node (ref "C49") (pin "1") (pinfunction "1_1") (pintype "passive"))
      (node (ref "C50") (pin "1") (pinfunction "1_1") (pintype "passive"))
      (node (ref "C51") (pin "1") (pinfunction "1_1") (pintype "passive"))
      (node (ref "C52") (pin "1") (pinfunction "1_1") (pintype "passive"))
      (node (ref "C53") (pin "1") (pinfunction "1_1") (pintype "passive"))
      (node (ref "C54") (pin "1") (pinfunction "1_1") (pintype "passive"))
      (node (ref "C55") (pin "1") (pinfunction "1_1") (pintype "passive"))
      (node (ref "C56") (pin "1") (pinfunction "1_1") (pintype "passive"))
      (node (ref "C57") (pin "1") (pinfunction "1_1") (pintype "passive"))
      (node (ref "C58") (pin "1") (pinfunction "1_1") (pintype "passive"))
      (node (ref "C59") (pin "1") (pinfunction "1_1") (pintype "passive"))
      (node (ref "C60") (pin "1") (pinfunction "1_1") (pintype "passive"))
      (node (ref "C61") (pin "1") (pinfunction "1_1") (pintype "passive"))
      (node (ref "C62") (pin "1") (pinfunction "1_1") (pintype "passive"))
      (node (ref "C63") (pin "1") (pinfunction "1_1") (pintype "passive"))
      (node (ref "C64") (pin "1") (pinfunction "1_1") (pintype "passive"))
      (node (ref "C65") (pin "1") (pinfunction "1_1") (pintype "passive"))
      (node (ref "C66") (pin "1") (pinfunction "1_1") (pintype "passive"))
      (node (ref "C67") (pin "1") (pinfunction "1_1") (pintype "passive"))
      (node (ref "C68") (pin "1") (pinfunction "1_1") (pintype "passive"))
      (node (ref "LED") (pin "2-VDD") (pinfunction "VDD_2-VDD") (pintype "input"))
      (node (ref "LED10") (pin "2-VDD") (pinfunction "VDD_2-VDD") (pintype "input"))
      (node (ref "LED11") (pin "2-VDD") (pinfunction "VDD_2-VDD") (pintype "input"))
      (node (ref "LED12") (pin "2-VDD") (pinfunction "VDD_2-VDD") (pintype "input"))
      (node (ref "LED13") (pin "2-VDD") (pinfunction "VDD_2-VDD") (pintype "input"))
      (node (ref "LED14") (pin "2-VDD") (pinfunction "VDD_2-VDD") (pintype "input"))
      (node (ref "LED15") (pin "2-VDD") (pinfunction "VDD_2-VDD") (pintype "input"))
      (node (ref "LED16") (pin "2-VDD") (pinfunction "VDD_2-VDD") (pintype "input"))
      (node (ref "LED17") (pin "2-VDD") (pinfunction "VDD_2-VDD") (pintype "input"))
      (node (ref "LED18") (pin "2-VDD") (pinfunction "VDD_2-VDD") (pintype "input"))
      (node (ref "LED19") (pin "2-VDD") (pinfunction "VDD_2-VDD") (pintype "input"))
      (node (ref "LED20") (pin "2-VDD") (pinfunction "VDD_2-VDD") (pintype "input"))
      (node (ref "LED21") (pin "2-VDD") (pinfunction "VDD_2-VDD") (pintype "input"))
      (node (ref "LED22") (pin "2-VDD") (pinfunction "VDD_2-VDD") (pintype "input"))
      (node (ref "LED23") (pin "2-VDD") (pinfunction "VDD_2-VDD") (pintype "input"))
      (node (ref "LED24") (pin "2-VDD") (pinfunction "VDD_2-VDD") (pintype "input"))
      (node (ref "LED25") (pin "2-VDD") (pinfunction "VDD_2-VDD") (pintype "input"))
      (node (ref "LED26") (pin "2-VDD") (pinfunction "VDD_2-VDD") (pintype "input"))
      (node (ref "LED27") (pin "2-VDD") (pinfunction "VDD_2-VDD") (pintype "input"))
      (node (ref "LED28") (pin "2-VDD") (pinfunction "VDD_2-VDD") (pintype "input"))
      (node (ref "LED29") (pin "2-VDD") (pinfunction "VDD_2-VDD") (pintype "input"))
      (node (ref "LED30") (pin "2-VDD") (pinfunction "VDD_2-VDD") (pintype "input"))
      (node (ref "LED31") (pin "2-VDD") (pinfunction "VDD_2-VDD") (pintype "input"))
      (node (ref "LED32") (pin "2-VDD") (pinfunction "VDD_2-VDD") (pintype "input"))
      (node (ref "LED33") (pin "2-VDD") (pinfunction "VDD_2-VDD") (pintype "input"))
      (node (ref "LED34") (pin "2-VDD") (pinfunction "VDD_2-VDD") (pintype "input"))
      (node (ref "LED35") (pin "2-VDD") (pinfunction "VDD_2-VDD") (pintype "input"))
      (node (ref "LED36") (pin "2-VDD") (pinfunction "VDD_2-VDD") (pintype "input"))
      (node (ref "LED37") (pin "2-VDD") (pinfunction "VDD_2-VDD") (pintype "input"))
      (node (ref "LED38") (pin "2-VDD") (pinfunction "VDD_2-VDD") (pintype "input"))
      (node (ref "LED39") (pin "2-VDD") (pinfunction "VDD_2-VDD") (pintype "input"))
      (node (ref "LED40") (pin "2-VDD") (pinfunction "VDD_2-VDD") (pintype "input"))
      (node (ref "LED41") (pin "2-VDD") (pinfunction "VDD_2-VDD") (pintype "input"))
      (node (ref "LED5") (pin "2-VDD") (pinfunction "VDD_2-VDD") (pintype "input"))
      (node (ref "LED6") (pin "2-VDD") (pinfunction "VDD_2-VDD") (pintype "input"))
      (node (ref "LED7") (pin "2-VDD") (pinfunction "VDD_2-VDD") (pintype "input"))
      (node (ref "LED8") (pin "2-VDD") (pinfunction "VDD_2-VDD") (pintype "input"))
      (node (ref "LED9") (pin "2-VDD") (pinfunction "VDD_2-VDD") (pintype "input"))
      (node (ref "Q8") (pin "6") (pinfunction "VOUT_6") (pintype "output"))
    )
    (net (code "5") (name "GND") (class "Default")
      (node (ref "C29") (pin "2") (pinfunction "2_2") (pintype "passive"))
      (node (ref "C30") (pin "2") (pinfunction "2_2") (pintype "passive"))
      (node (ref "C31") (pin "2") (pinfunction "2_2") (pintype "passive"))
      (node (ref "C32") (pin "2") (pinfunction "2_2") (pintype "passive"))
      (node (ref "C33") (pin "2") (pinfunction "2_2") (pintype "passive"))
      (node (ref "C34") (pin "2") (pinfunction "2_2") (pintype "passive"))
      (node (ref "C35") (pin "2") (pinfunction "2_2") (pintype "passive"))
      (node (ref "C36") (pin "2") (pinfunction "2_2") (pintype "passive"))
      (node (ref "C37") (pin "2") (pinfunction "2_2") (pintype "passive"))
      (node (ref "C38") (pin "2") (pinfunction "2_2") (pintype "passive"))
      (node (ref "C39") (pin "2") (pinfunction "2_2") (pintype "passive"))
      (node (ref "C40") (pin "2") (pinfunction "2_2") (pintype "passive"))
      (node (ref "C41") (pin "2") (pinfunction "2_2") (pintype "passive"))
      (node (ref "C42") (pin "2") (pinfunction "2_2") (pintype "passive"))
      (node (ref "C43") (pin "2") (pinfunction "2_2") (pintype "passive"))
      (node (ref "C44") (pin "2") (pinfunction "2_2") (pintype "passive"))
      (node (ref "C45") (pin "2") (pinfunction "2_2") (pintype "passive"))
      (node (ref "C46") (pin "2") (pinfunction "2_2") (pintype "passive"))
      (node (ref "C47") (pin "2") (pinfunction "2_2") (pintype "passive"))
      (node (ref "C48") (pin "2") (pinfunction "2_2") (pintype "passive"))
      (node (ref "C49") (pin "2") (pinfunction "2_2") (pintype "passive"))
      (node (ref "C50") (pin "2") (pinfunction "2_2") (pintype "passive"))
      (node (ref "C51") (pin "2") (pinfunction "2_2") (pintype "passive"))
      (node (ref "C52") (pin "2") (pinfunction "2_2") (pintype "passive"))
      (node (ref "C53") (pin "2") (pinfunction "2_2") (pintype "passive"))
      (node (ref "C54") (pin "2") (pinfunction "2_2") (pintype "passive"))
      (node (ref "C55") (pin "2") (pinfunction "2_2") (pintype "passive"))
      (node (ref "C56") (pin "2") (pinfunction "2_2") (pintype "passive"))
      (node (ref "C57") (pin "2") (pinfunction "2_2") (pintype "passive"))
      (node (ref "C58") (pin "2") (pinfunction "2_2") (pintype "passive"))
      (node (ref "C59") (pin "2") (pinfunction "2_2") (pintype "passive"))
      (node (ref "C60") (pin "2") (pinfunction "2_2") (pintype "passive"))
      (node (ref "C61") (pin "2") (pinfunction "2_2") (pintype "passive"))
      (node (ref "C62") (pin "2") (pinfunction "2_2") (pintype "passive"))
      (node (ref "C63") (pin "2") (pinfunction "2_2") (pintype "passive"))
      (node (ref "C64") (pin "2") (pinfunction "2_2") (pintype "passive"))
      (node (ref "C65") (pin "2") (pinfunction "2_2") (pintype "passive"))
      (node (ref "C66") (pin "2") (pinfunction "2_2") (pintype "passive"))
      (node (ref "C67") (pin "2") (pinfunction "2_2") (pintype "passive"))
      (node (ref "C68") (pin "2") (pinfunction "2_2") (pintype "passive"))
      (node (ref "LED") (pin "4-GND") (pinfunction "GND_4-GND") (pintype "power_in"))
      (node (ref "LED10") (pin "4-GND") (pinfunction "GND_4-GND") (pintype "power_in"))
      (node (ref "LED11") (pin "4-GND") (pinfunction "GND_4-GND") (pintype "power_in"))
      (node (ref "LED12") (pin "4-GND") (pinfunction "GND_4-GND") (pintype "power_in"))
      (node (ref "LED13") (pin "4-GND") (pinfunction "GND_4-GND") (pintype "power_in"))
      (node (ref "LED14") (pin "4-GND") (pinfunction "GND_4-GND") (pintype "power_in"))
      (node (ref "LED15") (pin "4-GND") (pinfunction "GND_4-GND") (pintype "power_in"))
      (node (ref "LED16") (pin "4-GND") (pinfunction "GND_4-GND") (pintype "power_in"))
      (node (ref "LED17") (pin "4-GND") (pinfunction "GND_4-GND") (pintype "power_in"))
      (node (ref "LED18") (pin "4-GND") (pinfunction "GND_4-GND") (pintype "power_in"))
      (node (ref "LED19") (pin "4-GND") (pinfunction "GND_4-GND") (pintype "power_in"))
      (node (ref "LED20") (pin "4-GND") (pinfunction "GND_4-GND") (pintype "power_in"))
      (node (ref "LED21") (pin "4-GND") (pinfunction "GND_4-GND") (pintype "power_in"))
      (node (ref "LED22") (pin "4-GND") (pinfunction "GND_4-GND") (pintype "power_in"))
      (node (ref "LED23") (pin "4-GND") (pinfunction "GND_4-GND") (pintype "power_in"))
      (node (ref "LED24") (pin "4-GND") (pinfunction "GND_4-GND") (pintype "power_in"))
      (node (ref "LED25") (pin "4-GND") (pinfunction "GND_4-GND") (pintype "power_in"))
      (node (ref "LED26") (pin "4-GND") (pinfunction "GND_4-GND") (pintype "power_in"))
      (node (ref "LED27") (pin "4-GND") (pinfunction "GND_4-GND") (pintype "power_in"))
      (node (ref "LED28") (pin "4-GND") (pinfunction "GND_4-GND") (pintype "power_in"))
      (node (ref "LED29") (pin "4-GND") (pinfunction "GND_4-GND") (pintype "power_in"))
      (node (ref "LED30") (pin "4-GND") (pinfunction "GND_4-GND") (pintype "power_in"))
      (node (ref "LED31") (pin "4-GND") (pinfunction "GND_4-GND") (pintype "power_in"))
      (node (ref "LED32") (pin "4-GND") (pinfunction "GND_4-GND") (pintype "power_in"))
      (node (ref "LED33") (pin "4-GND") (pinfunction "GND_4-GND") (pintype "power_in"))
      (node (ref "LED34") (pin "4-GND") (pinfunction "GND_4-GND") (pintype "power_in"))
      (node (ref "LED35") (pin "4-GND") (pinfunction "GND_4-GND") (pintype "power_in"))
      (node (ref "LED36") (pin "4-GND") (pinfunction "GND_4-GND") (pintype "power_in"))
      (node (ref "LED37") (pin "4-GND") (pinfunction "GND_4-GND") (pintype "power_in"))
      (node (ref "LED38") (pin "4-GND") (pinfunction "GND_4-GND") (pintype "power_in"))
      (node (ref "LED39") (pin "4-GND") (pinfunction "GND_4-GND") (pintype "power_in"))
      (node (ref "LED40") (pin "4-GND") (pinfunction "GND_4-GND") (pintype "power_in"))
      (node (ref "LED41") (pin "4-GND") (pinfunction "GND_4-GND") (pintype "power_in"))
      (node (ref "LED5") (pin "4-GND") (pinfunction "GND_4-GND") (pintype "power_in"))
      (node (ref "LED6") (pin "4-GND") (pinfunction "GND_4-GND") (pintype "power_in"))
      (node (ref "LED7") (pin "4-GND") (pinfunction "GND_4-GND") (pintype "power_in"))
      (node (ref "LED8") (pin "4-GND") (pinfunction "GND_4-GND") (pintype "power_in"))
      (node (ref "LED9") (pin "4-GND") (pinfunction "GND_4-GND") (pintype "power_in"))
      (node (ref "Q8") (pin "2") (pinfunction "GND_2") (pintype "power_in"))
    )
    (net (code "6") (name "Net-(LED-DO)") (class "Default")
      (node (ref "LED") (pin "1-DO") (pinfunction "DO_1-DO") (pintype "output"))
      (node (ref "LED5") (pin "3-DI") (pinfunction "DI_3-DI") (pintype "input"))
    )
    (net (code "7") (name "Net-(LED5-DO)") (class "Default")
      (node (ref "LED5") (pin "1-DO") (pinfunction "DO_1-DO") (pintype "output"))
      (node (ref "LED6") (pin "3-DI") (pinfunction "DI_3-DI") (pintype "input"))
    )
    (net (code "8") (name "Net-(LED6-DO)") (class "Default")
      (node (ref "LED6") (pin "1-DO") (pinfunction "DO_1-DO") (pintype "output"))
      (node (ref "LED7") (pin "3-DI") (pinfunction "DI_3-DI") (pintype "input"))
    )
    (net (code "9") (name "Net-(LED7-DO)") (class "Default")
      (node (ref "LED7") (pin "1-DO") (pinfunction "DO_1-DO") (pintype "output"))
      (node (ref "LED8") (pin "3-DI") (pinfunction "DI_3-DI") (pintype "input"))
    )
    (net (code "10") (name "Net-(LED8-DO)") (class "Default")
      (node (ref "LED8") (pin "1-DO") (pinfunction "DO_1-DO") (pintype "output"))
      (node (ref "LED9") (pin "3-DI") (pinfunction "DI_3-DI") (pintype "input"))
    )
    (net (code "11") (name "Net-(LED10-DI)") (class "Default")
      (node (ref "LED10") (pin "3-DI") (pinfunction "DI_3-DI") (pintype "input"))
      (node (ref "LED9") (pin "1-DO") (pinfunction "DO_1-DO") (pintype "output"))
    )
    (net (code "12") (name "Net-(LED10-DO)") (class "Default")
      (node (ref "LED10") (pin "1-DO") (pinfunction "DO_1-DO") (pintype "output"))
      (node (ref "LED11") (pin "3-DI") (pinfunction "DI_3-DI") (pintype "input"))
    )
    (net (code "13") (name "Net-(LED11-DO)") (class "Default")
      (node (ref "LED11") (pin "1-DO") (pinfunction "DO_1-DO") (pintype "output"))
      (node (ref "LED19") (pin "3-DI") (pinfunction "DI_3-DI") (pintype "input"))
    )
    (net (code "14") (name "Net-(LED12-DI)") (class "Default")
      (node (ref "LED12") (pin "3-DI") (pinfunction "DI_3-DI") (pintype "input"))
      (node (ref "LED13") (pin "1-DO") (pinfunction "DO_1-DO") (pintype "output"))
    )
    (net (code "15") (name "Net-(LED12-DO)") (class "Default")
      (node (ref "LED12") (pin "1-DO") (pinfunction "DO_1-DO") (pintype "output"))
      (node (ref "LED20") (pin "3-DI") (pinfunction "DI_3-DI") (pintype "input"))
    )
    (net (code "16") (name "Net-(LED13-DI)") (class "Default")
      (node (ref "LED13") (pin "3-DI") (pinfunction "DI_3-DI") (pintype "input"))
      (node (ref "LED14") (pin "1-DO") (pinfunction "DO_1-DO") (pintype "output"))
    )
    (net (code "17") (name "Net-(LED14-DI)") (class "Default")
      (node (ref "LED14") (pin "3-DI") (pinfunction "DI_3-DI") (pintype "input"))
      (node (ref "LED15") (pin "1-DO") (pinfunction "DO_1-DO") (pintype "output"))
    )
    (net (code "18") (name "Net-(LED15-DI)") (class "Default")
      (node (ref "LED15") (pin "3-DI") (pinfunction "DI_3-DI") (pintype "input"))
      (node (ref "LED16") (pin "1-DO") (pinfunction "DO_1-DO") (pintype "output"))
    )
    (net (code "19") (name "Net-(LED16-DI)") (class "Default")
      (node (ref "LED16") (pin "3-DI") (pinfunction "DI_3-DI") (pintype "input"))
      (node (ref "LED17") (pin "1-DO") (pinfunction "DO_1-DO") (pintype "output"))
    )
    (net (code "20") (name "Net-(LED17-DI)") (class "Default")
      (node (ref "LED17") (pin "3-DI") (pinfunction "DI_3-DI") (pintype "input"))
      (node (ref "LED18") (pin "1-DO") (pinfunction "DO_1-DO") (pintype "output"))
    )
    (net (code "21") (name "Net-(LED18-DI)") (class "Default")
      (node (ref "LED18") (pin "3-DI") (pinfunction "DI_3-DI") (pintype "input"))
      (node (ref "LED19") (pin "1-DO") (pinfunction "DO_1-DO") (pintype "output"))
    )
    (net (code "22") (name "Net-(LED20-DO)") (class "Default")
      (node (ref "LED20") (pin "1-DO") (pinfunction "DO_1-DO") (pintype "output"))
      (node (ref "LED21") (pin "3-DI") (pinfunction "DI_3-DI") (pintype "input"))
    )
    (net (code "23") (name "Net-(LED21-DO)") (class "Default")
      (node (ref "LED21") (pin "1-DO") (pinfunction "DO_1-DO") (pintype "output"))
      (node (ref "LED22") (pin "3-DI") (pinfunction "DI_3-DI") (pintype "input"))
    )
    (net (code "24") (name "Net-(LED22-DO)") (class "Default")
      (node (ref "LED22") (pin "1-DO") (pinfunction "DO_1-DO") (pintype "output"))
      (node (ref "LED23") (pin "3-DI") (pinfunction "DI_3-DI") (pintype "input"))
    )
    (net (code "25") (name "Net-(LED23-DO)") (class "Default")
      (node (ref "LED23") (pin "1-DO") (pinfunction "DO_1-DO") (pintype "output"))
      (node (ref "LED24") (pin "3-DI") (pinfunction "DI_3-DI") (pintype "input"))
    )
    (net (code "26") (name "Net-(LED24-DO)") (class "Default")
      (node (ref "LED24") (pin "1-DO") (pinfunction "DO_1-DO") (pintype "output"))
      (node (ref "LED25") (pin "3-DI") (pinfunction "DI_3-DI") (pintype "input"))
    )
    (net (code "27") (name "Net-(LED25-DO)") (class "Default")
      (node (ref "LED25") (pin "1-DO") (pinfunction "DO_1-DO") (pintype "output"))
      (node (ref "LED26") (pin "3-DI") (pinfunction "DI_3-DI") (pintype "input"))
    )
    (net (code "28") (name "Net-(LED26-DO)") (class "Default")
      (node (ref "LED26") (pin "1-DO") (pinfunction "DO_1-DO") (pintype "output"))
      (node (ref "LED27") (pin "3-DI") (pinfunction "DI_3-DI") (pintype "input"))
    )
    (net (code "29") (name "Net-(LED27-DO)") (class "Default")
      (node (ref "LED27") (pin "1-DO") (pinfunction "DO_1-DO") (pintype "output"))
      (node (ref "LED34") (pin "3-DI") (pinfunction "DI_3-DI") (pintype "input"))
    )
    (net (code "30") (name "Net-(LED28-DI)") (class "Default")
      (node (ref "LED28") (pin "3-DI") (pinfunction "DI_3-DI") (pintype "input"))
      (node (ref "LED29") (pin "1-DO") (pinfunction "DO_1-DO") (pintype "output"))
    )
    (net (code "31") (name "Net-(LED28-DO)") (class "Default")
      (node (ref "LED28") (pin "1-DO") (pinfunction "DO_1-DO") (pintype "output"))
      (node (ref "LED35") (pin "3-DI") (pinfunction "DI_3-DI") (pintype "input"))
    )
    (net (code "32") (name "Net-(LED29-DI)") (class "Default")
      (node (ref "LED29") (pin "3-DI") (pinfunction "DI_3-DI") (pintype "input"))
      (node (ref "LED30") (pin "1-DO") (pinfunction "DO_1-DO") (pintype "output"))
    )
    (net (code "33") (name "Net-(LED30-DI)") (class "Default")
      (node (ref "LED30") (pin "3-DI") (pinfunction "DI_3-DI") (pintype "input"))
      (node (ref "LED31") (pin "1-DO") (pinfunction "DO_1-DO") (pintype "output"))
    )
    (net (code "34") (name "Net-(LED31-DI)") (class "Default")
      (node (ref "LED31") (pin "3-DI") (pinfunction "DI_3-DI") (pintype "input"))
      (node (ref "LED32") (pin "1-DO") (pinfunction "DO_1-DO") (pintype "output"))
    )
    (net (code "35") (name "Net-(LED32-DI)") (class "Default")
      (node (ref "LED32") (pin "3-DI") (pinfunction "DI_3-DI") (pintype "input"))
      (node (ref "LED33") (pin "1-DO") (pinfunction "DO_1-DO") (pintype "output"))
    )
    (net (code "36") (name "Net-(LED33-DI)") (class "Default")
      (node (ref "LED33") (pin "3-DI") (pinfunction "DI_3-DI") (pintype "input"))
      (node (ref "LED34") (pin "1-DO") (pinfunction "DO_1-DO") (pintype "output"))
    )
    (net (code "37") (name "Net-(LED35-DO)") (class "Default")
      (node (ref "LED35") (pin "1-DO") (pinfunction "DO_1-DO") (pintype "output"))
      (node (ref "LED36") (pin "3-DI") (pinfunction "DI_3-DI") (pintype "input"))
    )
    (net (code "38") (name "Net-(LED36-DO)") (class "Default")
      (node (ref "LED36") (pin "1-DO") (pinfunction "DO_1-DO") (pintype "output"))
      (node (ref "LED37") (pin "3-DI") (pinfunction "DI_3-DI") (pintype "input"))
    )
    (net (code "39") (name "Net-(LED37-DO)") (class "Default")
      (node (ref "LED37") (pin "1-DO") (pinfunction "DO_1-DO") (pintype "output"))
      (node (ref "LED38") (pin "3-DI") (pinfunction "DI_3-DI") (pintype "input"))
    )
    (net (code "40") (name "Net-(LED38-DO)") (class "Default")
      (node (ref "LED38") (pin "1-DO") (pinfunction "DO_1-DO") (pintype "output"))
      (node (ref "LED39") (pin "3-DI") (pinfunction "DI_3-DI") (pintype "input"))
    )
    (net (code "41") (name "Net-(LED39-DO)") (class "Default")
      (node (ref "LED39") (pin "1-DO") (pinfunction "DO_1-DO") (pintype "output"))
      (node (ref "LED40") (pin "3-DI") (pinfunction "DI_3-DI") (pintype "input"))
    )
    (net (code "42") (name "Net-(LED40-DO)") (class "Default")
      (node (ref "LED40") (pin "1-DO") (pinfunction "DO_1-DO") (pintype "output"))
      (node (ref "LED41") (pin "3-DI") (pinfunction "DI_3-DI") (pintype "input"))
    )
    (net (code "43") (name "Net-(Q8-ON)") (class "Default")
      (node (ref "Q8") (pin "3") (pinfunction "ON_3") (pintype "bidirectional"))
      (node (ref "R37") (pin "1") (pinfunction "1_1") (pintype "passive"))
    )
    (net (code "44") (name "VMCU") (class "Default")
      (node (ref "C29") (pin "1") (pinfunction "1_1") (pintype "passive"))
      (node (ref "Q8") (pin "1") (pinfunction "IN_1") (pintype "input"))
    )
    (net (code "45") (name "unconnected-(LED41-DO-Pad1-DO)") (class "Default")
      (node (ref "LED41") (pin "1-DO") (pinfunction "DO_1-DO") (pintype "output+no_connect"))
    )
    (net (code "46") (name "unconnected-(Q8-QOD-Pad5)") (class "Default")
      (node (ref "Q8") (pin "5") (pinfunction "QOD_5") (pintype "output+no_connect"))
    )
  )
)
